# PWR_TPS54623_0v9_5A.net
KiCad netlist of a schematic drawn in Altium Designer
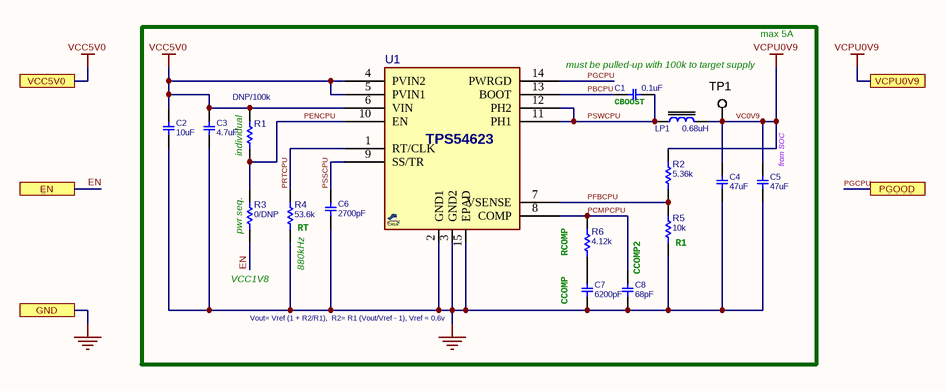
[diagram p0: PWR_TPS54623_0v9_5A.SchDoc]

(export (version "E")
  (design (tool "Eeschema 10.0.6"))
  (components
    (comp (ref "C1")
      (value "0.1uF")
      (footprint "C0402")
      (description "CAP, MLCC, 100nF, 50V, X7R, 10%, 0402C")
      (fields (field (name "MANF") "Murata") (field (name "MANF_P#") "GRM155R61E104"))
      (libsource (lib "passive_mlcc_smd") (part "CAP_SMD_MLCC_100n50V"))
    )
    (comp (ref "C2")
      (value "10uF")
      (footprint "C0402")
      (description "CAP, MLCC")
      (fields (field (name "MANF_P#") "CL05A106MP5NUNC") (field (name "MANF") "Samsung"))
      (libsource (lib "passive_smd") (part "CAP_SMD_MLCC"))
    )
    (comp (ref "C3")
      (value "4.7uF")
      (footprint "C0402")
      (description "CAP, MLCC")
      (fields (field (name "MANF_P#") "CL05A475MP5NRNC") (field (name "MANF") "Samsung"))
      (libsource (lib "passive_smd") (part "CAP_SMD_MLCC"))
    )
    (comp (ref "C4")
      (value "47uF")
      (footprint "C0805")
      (description "CAP, MLCC, X5R 47uF 25V 20% 1206")
      (fields (field (name "MANF") "Samsung") (field (name "MANF_P#") "CL21A476MQYNNNE"))
      (libsource (lib "passive_mlcc_smd") (part "CAP_SMD_MLCC_47u25V"))
    )
    (comp (ref "C5")
      (value "47uF")
      (footprint "C0805")
      (description "CAP, MLCC, X5R 47uF 25V 20% 1206")
      (fields (field (name "MANF") "Samsung") (field (name "MANF_P#") "CL21A476MQYNNNE"))
      (libsource (lib "passive_mlcc_smd") (part "CAP_SMD_MLCC_47u25V"))
    )
    (comp (ref "C6")
      (value "2700pF")
      (footprint "C0402")
      (description "CAP, MLCC, 0402C")
      (libsource (lib "passive_mlcc_smd") (part "CAP_SMD_MLCC_100n50V"))
    )
    (comp (ref "C7")
      (value "6200pF")
      (footprint "C0402")
      (description "CAP, MLCC, 0402C")
      (libsource (lib "passive_mlcc_smd") (part "CAP_SMD_MLCC_100n50V"))
    )
    (comp (ref "C8")
      (value "68pF")
      (footprint "C0402")
      (description "CAP, MLCC, 0402C")
      (libsource (lib "passive_mlcc_smd") (part "CAP_SMD_MLCC_100n50V"))
    )
    (comp (ref "LP1")
      (value "0.68uH")
      (footprint "L_5")
      (description "INDUCTOR, 3.3uH, 8A (Irms), 10mOhm")
      (fields (field (name "MANF_P#") "MDWK4040TR68MM"))
      (libsource (lib "chila_passive") (part "IND_SMD_2.2uH_4A"))
    )
    (comp (ref "R1")
      (value "DNP/100k")
      (footprint "R0402")
      (description "RESISTOR, SMD, 20K, 0402")
      (libsource (lib "chila_passive") (part "RES_SMD"))
    )
    (comp (ref "R2")
      (value "5.36k")
      (footprint "R0402")
      (description "RESISTOR, SMD, 20K, 0402")
      (libsource (lib "chila_passive") (part "RES_SMD"))
    )
    (comp (ref "R3")
      (value "0/DNP")
      (footprint "R0402")
      (description "RESISTOR, SMD, 20K, 0402")
      (libsource (lib "chila_passive") (part "RES_SMD"))
    )
    (comp (ref "R4")
      (value "53.6k")
      (footprint "R0402")
      (description "RESISTOR, SMD, 20K, 0402")
      (libsource (lib "chila_passive") (part "RES_SMD"))
    )
    (comp (ref "R5")
      (value "10k")
      (footprint "R0402")
      (description "RESISTOR, SMD, 20K, 0402")
      (libsource (lib "chila_passive") (part "RES_SMD"))
    )
    (comp (ref "R6")
      (value "4.12k")
      (footprint "R0402")
      (description "RESISTOR, SMD, 20K, 0402")
      (libsource (lib "chila_passive") (part "RES_SMD"))
    )
    (comp (ref "TP1")
      (value "TESTPOINT_SMD")
      (footprint "TPSMD_S1")
      (description "TEST POINT")
      (fields (field (name "MANF") "MANF") (field (name "MANF_P#") "MANF_P#"))
      (libsource (lib "test-tp_jumper") (part "TESTPOINT_SMD"))
    )
    (comp (ref "U1")
      (value "TPS54623")
      (footprint "QFN50_14T_3535")
      (description "REG, Switching, Buck, 6A, ADJ, 1.6MHz, 4.5~17Vin, VQFN-14")
      (fields (field (name "MANF") "TI") (field (name "MANF_P#") "TPS54623RHL"))
      (libsource (lib "pwr_switching_buck") (part "VREG_TPS54623_VQFN14"))
    )
  )
  (nets
    (net (code "1") (name "/EN") (class "Default")
      (node (ref "R3") (pin "2") (pinfunction "2_2") (pintype "passive"))
    )
    (net (code "2") (name "/PBCPU") (class "Default")
      (node (ref "C1") (pin "1") (pinfunction "1_1") (pintype "passive"))
      (node (ref "U1") (pin "13") (pinfunction "BOOT_13") (pintype "passive"))
    )
    (net (code "3") (name "/PCMPCPU") (class "Default")
      (node (ref "C8") (pin "1") (pinfunction "1_1") (pintype "passive"))
      (node (ref "R6") (pin "1") (pinfunction "1_1") (pintype "passive"))
      (node (ref "U1") (pin "8") (pinfunction "COMP_8") (pintype "passive"))
    )
    (net (code "4") (name "/PENCPU") (class "Default")
      (node (ref "R1") (pin "2") (pinfunction "2_2") (pintype "passive"))
      (node (ref "R3") (pin "1") (pinfunction "1_1") (pintype "passive"))
      (node (ref "U1") (pin "10") (pinfunction "EN_10") (pintype "passive"))
    )
    (net (code "5") (name "/PFBCPU") (class "Default")
      (node (ref "R2") (pin "2") (pinfunction "2_2") (pintype "passive"))
      (node (ref "R5") (pin "1") (pinfunction "1_1") (pintype "passive"))
      (node (ref "U1") (pin "7") (pinfunction "VSENSE_7") (pintype "passive"))
    )
    (net (code "6") (name "/PGCPU") (class "Default")
      (node (ref "U1") (pin "14") (pinfunction "PWRGD_14") (pintype "passive"))
    )
    (net (code "7") (name "/PRTCPU") (class "Default")
      (node (ref "R4") (pin "1") (pinfunction "1_1") (pintype "passive"))
      (node (ref "U1") (pin "1") (pinfunction "RT/CLK_1") (pintype "passive"))
    )
    (net (code "8") (name "/PSSCPU") (class "Default")
      (node (ref "C6") (pin "1") (pinfunction "1_1") (pintype "passive"))
      (node (ref "U1") (pin "9") (pinfunction "SS/TR_9") (pintype "passive"))
    )
    (net (code "9") (name "/PSWCPU") (class "Default")
      (node (ref "C1") (pin "2") (pinfunction "2_2") (pintype "passive"))
      (node (ref "LP1") (pin "1") (pinfunction "1_1") (pintype "passive"))
      (node (ref "U1") (pin "11") (pinfunction "PH1_11") (pintype "passive"))
      (node (ref "U1") (pin "12") (pinfunction "PH2_12") (pintype "passive"))
    )
    (net (code "10") (name "GND") (class "Default")
      (node (ref "C2") (pin "1") (pinfunction "1_1") (pintype "passive"))
      (node (ref "C3") (pin "1") (pinfunction "1_1") (pintype "passive"))
      (node (ref "C4") (pin "2") (pinfunction "2_2") (pintype "passive"))
      (node (ref "C5") (pin "2") (pinfunction "2_2") (pintype "passive"))
      (node (ref "C6") (pin "2") (pinfunction "2_2") (pintype "passive"))
      (node (ref "C7") (pin "2") (pinfunction "2_2") (pintype "passive"))
      (node (ref "C8") (pin "2") (pinfunction "2_2") (pintype "passive"))
      (node (ref "R4") (pin "2") (pinfunction "2_2") (pintype "passive"))
      (node (ref "R5") (pin "2") (pinfunction "2_2") (pintype "passive"))
      (node (ref "U1") (pin "15") (pinfunction "EPAD_15") (pintype "passive"))
      (node (ref "U1") (pin "2") (pinfunction "GND1_2") (pintype "passive"))
      (node (ref "U1") (pin "3") (pinfunction "GND2_3") (pintype "passive"))
    )
    (net (code "11") (name "Net-(C7-Pad1)") (class "Default")
      (node (ref "C7") (pin "1") (pinfunction "1_1") (pintype "passive"))
      (node (ref "R6") (pin "2") (pinfunction "2_2") (pintype "passive"))
    )
    (net (code "12") (name "VCC5V0") (class "Default")
      (node (ref "C2") (pin "2") (pinfunction "2_2") (pintype "passive"))
      (node (ref "C3") (pin "2") (pinfunction "2_2") (pintype "passive"))
      (node (ref "R1") (pin "1") (pinfunction "1_1") (pintype "passive"))
      (node (ref "U1") (pin "4") (pinfunction "PVIN2_4") (pintype "passive"))
      (node (ref "U1") (pin "5") (pinfunction "PVIN1_5") (pintype "passive"))
      (node (ref "U1") (pin "6") (pinfunction "VIN_6") (pintype "passive"))
    )
    (net (code "13") (name "VCPU0V9") (class "Default")
      (node (ref "C4") (pin "1") (pinfunction "1_1") (pintype "passive"))
      (node (ref "C5") (pin "1") (pinfunction "1_1") (pintype "passive"))
      (node (ref "LP1") (pin "2") (pinfunction "2_2") (pintype "passive"))
      (node (ref "R2") (pin "1") (pinfunction "1_1") (pintype "passive"))
      (node (ref "TP1") (pin "1") (pinfunction "1_1") (pintype "passive"))
    )
  )
)
